# LM2596-4V.net
KiCad netlist of a schematic drawn in Altium Designer
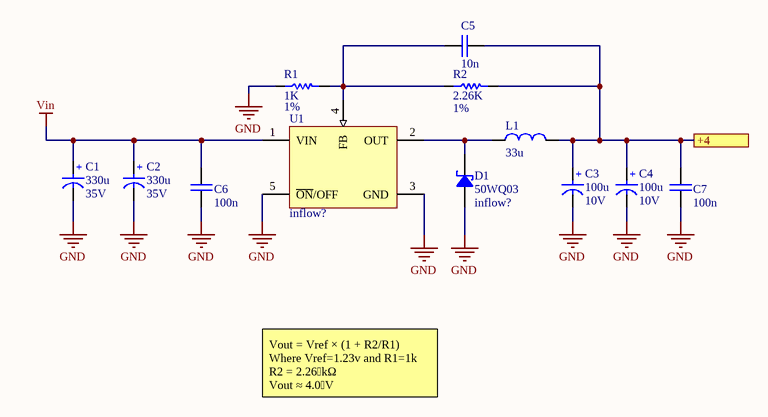
[diagram p0: LM2596-4V.SchDoc]

(export (version "E")
  (design (tool "Eeschema 10.0.6"))
  (components
    (comp (ref "C1")
      (value "330u")
      (footprint "CAP ALUM 10.3MM")
      (description "Electrolit Capacitor SMD")
      (fields (field (name "RATING") "35V"))
      (libsource (lib "aKaReZa") (part "Cap_Electrolit_SMD"))
    )
    (comp (ref "C2")
      (value "330u")
      (footprint "CAP ALUM 10.3MM")
      (description "Electrolit Capacitor SMD")
      (fields (field (name "RATING") "35V"))
      (libsource (lib "aKaReZa") (part "Cap_Electrolit_SMD"))
    )
    (comp (ref "C3")
      (value "100u")
      (footprint "CAP ALUM 10.3MM")
      (description "Electrolit Capacitor SMD")
      (fields (field (name "RATING") "10V"))
      (libsource (lib "aKaReZa") (part "Cap_Electrolit_SMD"))
    )
    (comp (ref "C4")
      (value "100u")
      (footprint "CAP ALUM 10.3MM")
      (description "Electrolit Capacitor SMD")
      (fields (field (name "RATING") "10V"))
      (libsource (lib "aKaReZa") (part "Cap_Electrolit_SMD"))
    )
    (comp (ref "C5")
      (value "10n")
      (footprint "CAP 1206/3216")
      (description "Bipolar ceramic capacitor SMD")
      (fields (field (name "VALIDATION") "Valid"))
      (libsource (lib "aKaReZa") (part "Cap_Multi_SMD_100nF_1206"))
    )
    (comp (ref "C6")
      (value "100n")
      (footprint "CAP 1206/3216")
      (description "Bipolar ceramic capacitor SMD")
      (fields (field (name "VALIDATION") "Valid"))
      (libsource (lib "aKaReZa") (part "Cap_Multi_SMD_100nF_1206"))
    )
    (comp (ref "C7")
      (value "100n")
      (footprint "CAP 1206/3216")
      (description "Bipolar ceramic capacitor SMD")
      (fields (field (name "VALIDATION") "Valid"))
      (libsource (lib "aKaReZa") (part "Cap_Multi_SMD_100nF_1206"))
    )
    (comp (ref "D1")
      (value "50WQ03")
      (footprint "50WQ03")
      (description "Fast soft recovery power rectifier")
      (fields (field (name "INFLOW") "inflow?"))
      (libsource (lib "aKaReZa") (part "Semi_Diod_Sch_50WQ03"))
    )
    (comp (ref "L1")
      (value "33u")
      (footprint "L_12")
      (description "Inductor")
      (libsource (lib "aKaReZa") (part "Ind_SMD"))
    )
    (comp (ref "R1")
      (value "1K")
      (footprint "Res-(1/4)")
      (description "Resistor")
      (fields (field (name "TYPE") "1%"))
      (libsource (lib "aKaReZa") (part "Res_Dip_0.25"))
    )
    (comp (ref "R2")
      (value "2.26K")
      (footprint "Res-(1/4)")
      (description "Resistor")
      (fields (field (name "TYPE") "1%"))
      (libsource (lib "aKaReZa") (part "Res_Dip_0.25"))
    )
    (comp (ref "U1")
      (value "Adj")
      (footprint "D2PAK_TO-263-5")
      (description "Simple switcher 3'A step-down voltage regulator")
      (fields (field (name "INFLOW") "inflow?"))
      (libsource (lib "aKaReZa") (part "IC_Reg_LM2596"))
    )
  )
  (nets
    (net (code "1") (name "/+4") (class "Default")
      (node (ref "C3") (pin "1") (pinfunction "+_1") (pintype "passive"))
      (node (ref "C4") (pin "1") (pinfunction "+_1") (pintype "passive"))
      (node (ref "C5") (pin "2") (pinfunction "2_2") (pintype "passive"))
      (node (ref "C7") (pin "1") (pinfunction "1_1") (pintype "passive"))
      (node (ref "L1") (pin "2") (pinfunction "2_2") (pintype "passive"))
      (node (ref "R2") (pin "2") (pinfunction "2_2") (pintype "passive"))
    )
    (net (code "2") (name "GND") (class "Default")
      (node (ref "C1") (pin "2") (pinfunction "-_2") (pintype "passive"))
      (node (ref "C2") (pin "2") (pinfunction "-_2") (pintype "passive"))
      (node (ref "C3") (pin "2") (pinfunction "-_2") (pintype "passive"))
      (node (ref "C4") (pin "2") (pinfunction "-_2") (pintype "passive"))
      (node (ref "C6") (pin "2") (pinfunction "2_2") (pintype "passive"))
      (node (ref "C7") (pin "2") (pinfunction "2_2") (pintype "passive"))
      (node (ref "D1") (pin "1") (pinfunction "1_1") (pintype "passive"))
      (node (ref "R1") (pin "1") (pinfunction "1_1") (pintype "passive"))
      (node (ref "U1") (pin "3") (pinfunction "GND_3") (pintype "power_in"))
      (node (ref "U1") (pin "5") (pinfunction "~{ON}/OFF_5") (pintype "power_in"))
    )
    (net (code "3") (name "Net-(U1-FB)") (class "Default")
      (node (ref "C5") (pin "1") (pinfunction "1_1") (pintype "passive"))
      (node (ref "R1") (pin "2") (pinfunction "2_2") (pintype "passive"))
      (node (ref "R2") (pin "1") (pinfunction "1_1") (pintype "passive"))
      (node (ref "U1") (pin "4") (pinfunction "FB_4") (pintype "input"))
    )
    (net (code "4") (name "Net-(U1-OUT)") (class "Default")
      (node (ref "D1") (pin "2") (pinfunction "2_2") (pintype "passive"))
      (node (ref "L1") (pin "1") (pinfunction "1_1") (pintype "passive"))
      (node (ref "U1") (pin "2") (pinfunction "OUT_2") (pintype "power_in"))
    )
    (net (code "5") (name "Vin") (class "Default")
      (node (ref "C1") (pin "1") (pinfunction "+_1") (pintype "passive"))
      (node (ref "C2") (pin "1") (pinfunction "+_1") (pintype "passive"))
      (node (ref "C6") (pin "1") (pinfunction "1_1") (pintype "passive"))
      (node (ref "U1") (pin "1") (pinfunction "VIN_1") (pintype "power_in"))
    )
  )
)
